# 03_SENSORS.net
KiCad netlist of a schematic drawn in Altium Designer
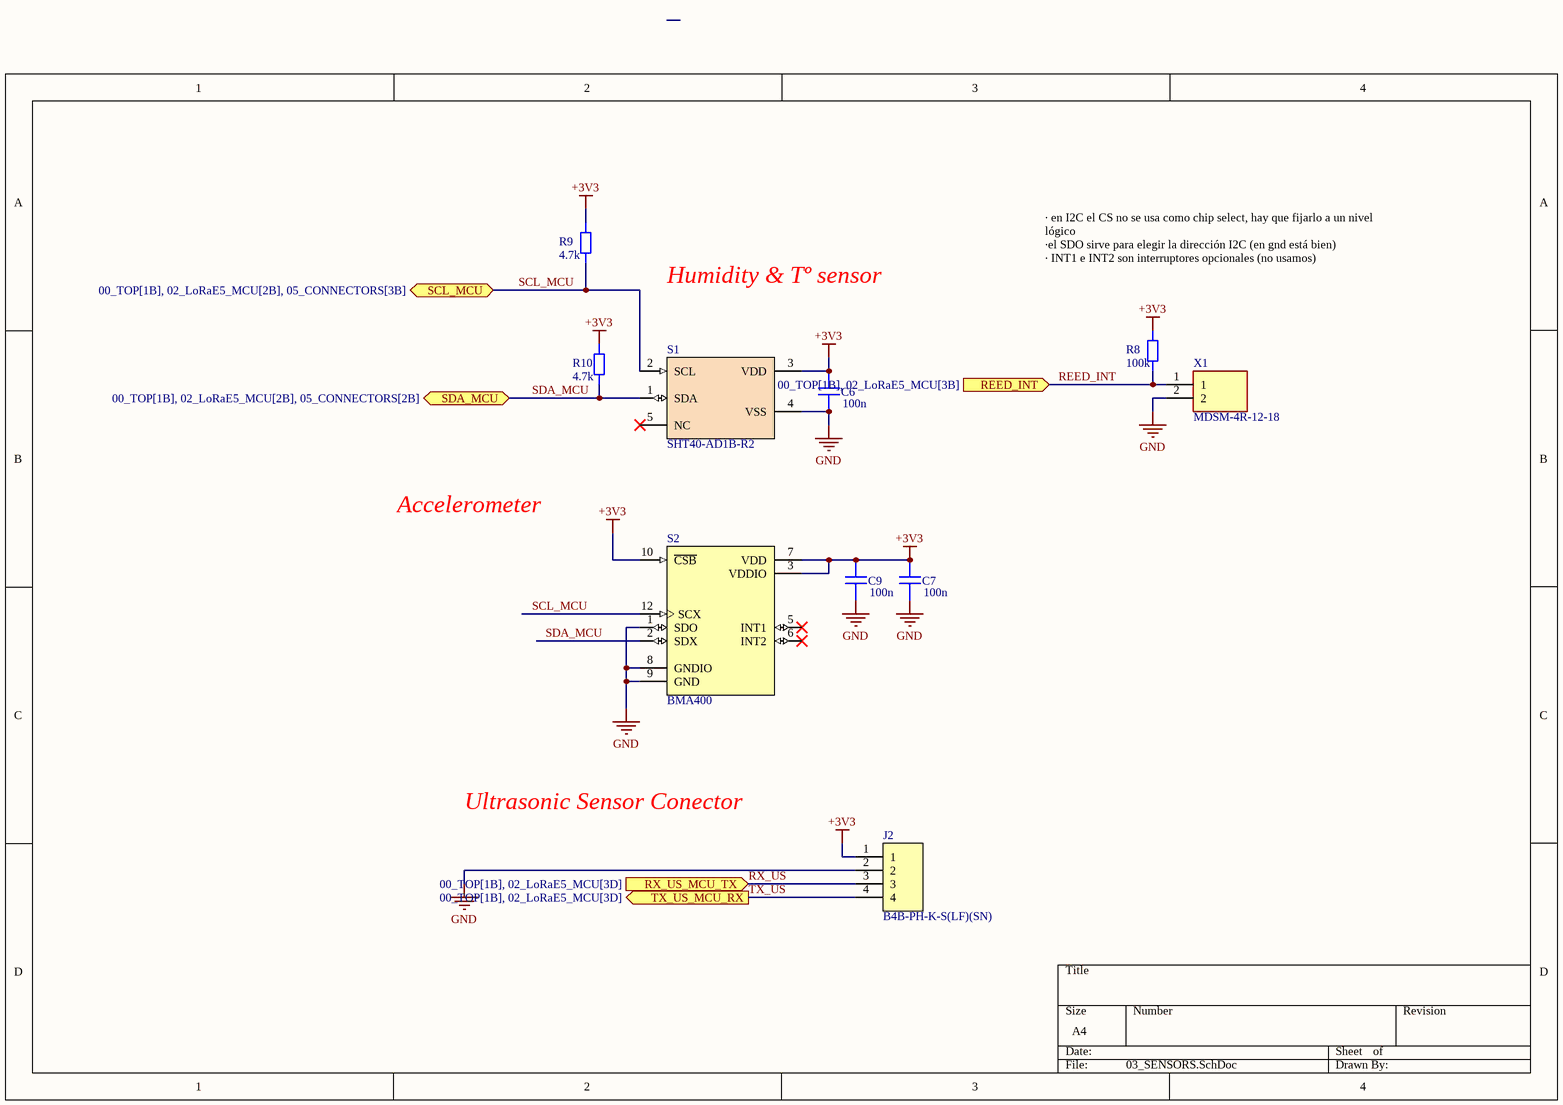
[diagram p0: 03_SENSORS.SchDoc]

(export (version "E")
  (design (tool "Eeschema 10.0.6"))
  (components
    (comp (ref "C6")
      (value "100n")
      (footprint "Capacitor_SMD:0603_1608m")
      (libsource (lib "TrashTrack_SCH_LIB") (part "Generic_Capacitor"))
    )
    (comp (ref "C7")
      (value "100n")
      (footprint "Capacitor_SMD:0603_1608m")
      (libsource (lib "TrashTrack_SCH_LIB") (part "Generic_Capacitor"))
    )
    (comp (ref "C9")
      (value "100n")
      (footprint "Capacitor_SMD:0603_1608m")
      (libsource (lib "TrashTrack_SCH_LIB") (part "Generic_Capacitor"))
    )
    (comp (ref "J2")
      (value "B4B-PH-K-S(LF)(SN)")
      (footprint "B4B-PH-K-S(LF)(SN)")
      (libsource (lib "TrashTrack_SCH_LIB") (part "B4B-PH-K-S(LF)(SN)"))
    )
    (comp (ref "R8")
      (value "100k")
      (footprint "Resistor_SMD:0603_1608m")
      (libsource (lib "TrashTrack_SCH_LIB") (part "Generic Resistor"))
    )
    (comp (ref "R9")
      (value "4.7k")
      (footprint "Resistor_SMD:0603_1608m")
      (libsource (lib "TrashTrack_SCH_LIB") (part "Generic Resistor"))
    )
    (comp (ref "R10")
      (value "4.7k")
      (footprint "Resistor_SMD:0603_1608m")
      (libsource (lib "TrashTrack_SCH_LIB") (part "Generic Resistor"))
    )
    (comp (ref "S1")
      (value "SHT40-AD1B-R2")
      (footprint "SHT4x_SEN")
      (libsource (lib "TrashTrack_SCH_LIB") (part "SHT40-AD1B-R2"))
    )
    (comp (ref "S2")
      (value "BMA400")
      (footprint "BMA400")
      (libsource (lib "TrashTrack_SCH_LIB") (part "BMA400"))
    )
    (comp (ref "X1")
      (value "MDSM-4R-12-18")
      (footprint "MDSM4R1218")
      (description "LITTELFUSE - MDSM-4R-12-18 - REED SW, SPST-NO, 0.5A, 200VDC, SMD")
      (fields (field (name "MOUSER PART NUMBER") "934-MDSM-4R12-18"))
      (libsource (lib "TrashTrack_SCH_LIB") (part "MDSM-4R-12-18"))
    )
  )
  (nets
    (net (code "1") (name "+3V3") (class "Default")
      (node (ref "C6") (pin "1") (pintype "passive"))
      (node (ref "C7") (pin "1") (pintype "passive"))
      (node (ref "C9") (pin "1") (pintype "passive"))
      (node (ref "J2") (pin "1") (pinfunction "1_1") (pintype "passive"))
      (node (ref "R10") (pin "1") (pintype "passive"))
      (node (ref "R8") (pin "1") (pintype "passive"))
      (node (ref "R9") (pin "1") (pintype "passive"))
      (node (ref "S1") (pin "3") (pinfunction "VDD_3") (pintype "power_in"))
      (node (ref "S2") (pin "10") (pinfunction "~{CSB}_10") (pintype "input"))
      (node (ref "S2") (pin "3") (pinfunction "VDDIO_3") (pintype "power_in"))
      (node (ref "S2") (pin "7") (pinfunction "VDD_7") (pintype "power_in"))
    )
    (net (code "2") (name "/REED_INT") (class "Default")
      (node (ref "R8") (pin "2") (pintype "passive"))
      (node (ref "X1") (pin "1") (pinfunction "1_1") (pintype "passive"))
    )
    (net (code "3") (name "/RX_US") (class "Default")
      (node (ref "J2") (pin "3") (pinfunction "3_3") (pintype "passive"))
    )
    (net (code "4") (name "/SCL_MCU") (class "Default")
      (node (ref "R9") (pin "2") (pintype "passive"))
      (node (ref "S1") (pin "2") (pinfunction "SCL_2") (pintype "input"))
      (node (ref "S2") (pin "12") (pinfunction "SCX_12") (pintype "input"))
    )
    (net (code "5") (name "/SDA_MCU") (class "Default")
      (node (ref "R10") (pin "2") (pintype "passive"))
      (node (ref "S1") (pin "1") (pinfunction "SDA_1") (pintype "bidirectional"))
      (node (ref "S2") (pin "2") (pinfunction "SDX_2") (pintype "bidirectional"))
    )
    (net (code "6") (name "/TX_US") (class "Default")
      (node (ref "J2") (pin "4") (pinfunction "4_4") (pintype "passive"))
    )
    (net (code "7") (name "GND") (class "Default")
      (node (ref "C6") (pin "2") (pintype "passive"))
      (node (ref "C7") (pin "2") (pintype "passive"))
      (node (ref "C9") (pin "2") (pintype "passive"))
      (node (ref "J2") (pin "2") (pinfunction "2_2") (pintype "passive"))
      (node (ref "S1") (pin "4") (pinfunction "VSS_4") (pintype "power_in"))
      (node (ref "S2") (pin "1") (pinfunction "SDO_1") (pintype "bidirectional"))
      (node (ref "S2") (pin "8") (pinfunction "GNDIO_8") (pintype "power_in"))
      (node (ref "S2") (pin "9") (pinfunction "GND_9") (pintype "power_in"))
      (node (ref "X1") (pin "2") (pinfunction "2_2") (pintype "passive"))
    )
    (net (code "8") (name "unconnected-(S1-NC-Pad5)") (class "Default")
      (node (ref "S1") (pin "5") (pinfunction "NC_5") (pintype "passive+no_connect"))
    )
    (net (code "9") (name "unconnected-(S2-INT1-Pad5)") (class "Default")
      (node (ref "S2") (pin "5") (pinfunction "INT1_5") (pintype "bidirectional+no_connect"))
    )
    (net (code "10") (name "unconnected-(S2-INT2-Pad6)") (class "Default")
      (node (ref "S2") (pin "6") (pinfunction "INT2_6") (pintype "bidirectional+no_connect"))
    )
  )
)
